# data_proV2_0_-_A.net
KiCad netlist of a schematic drawn in EAGLE
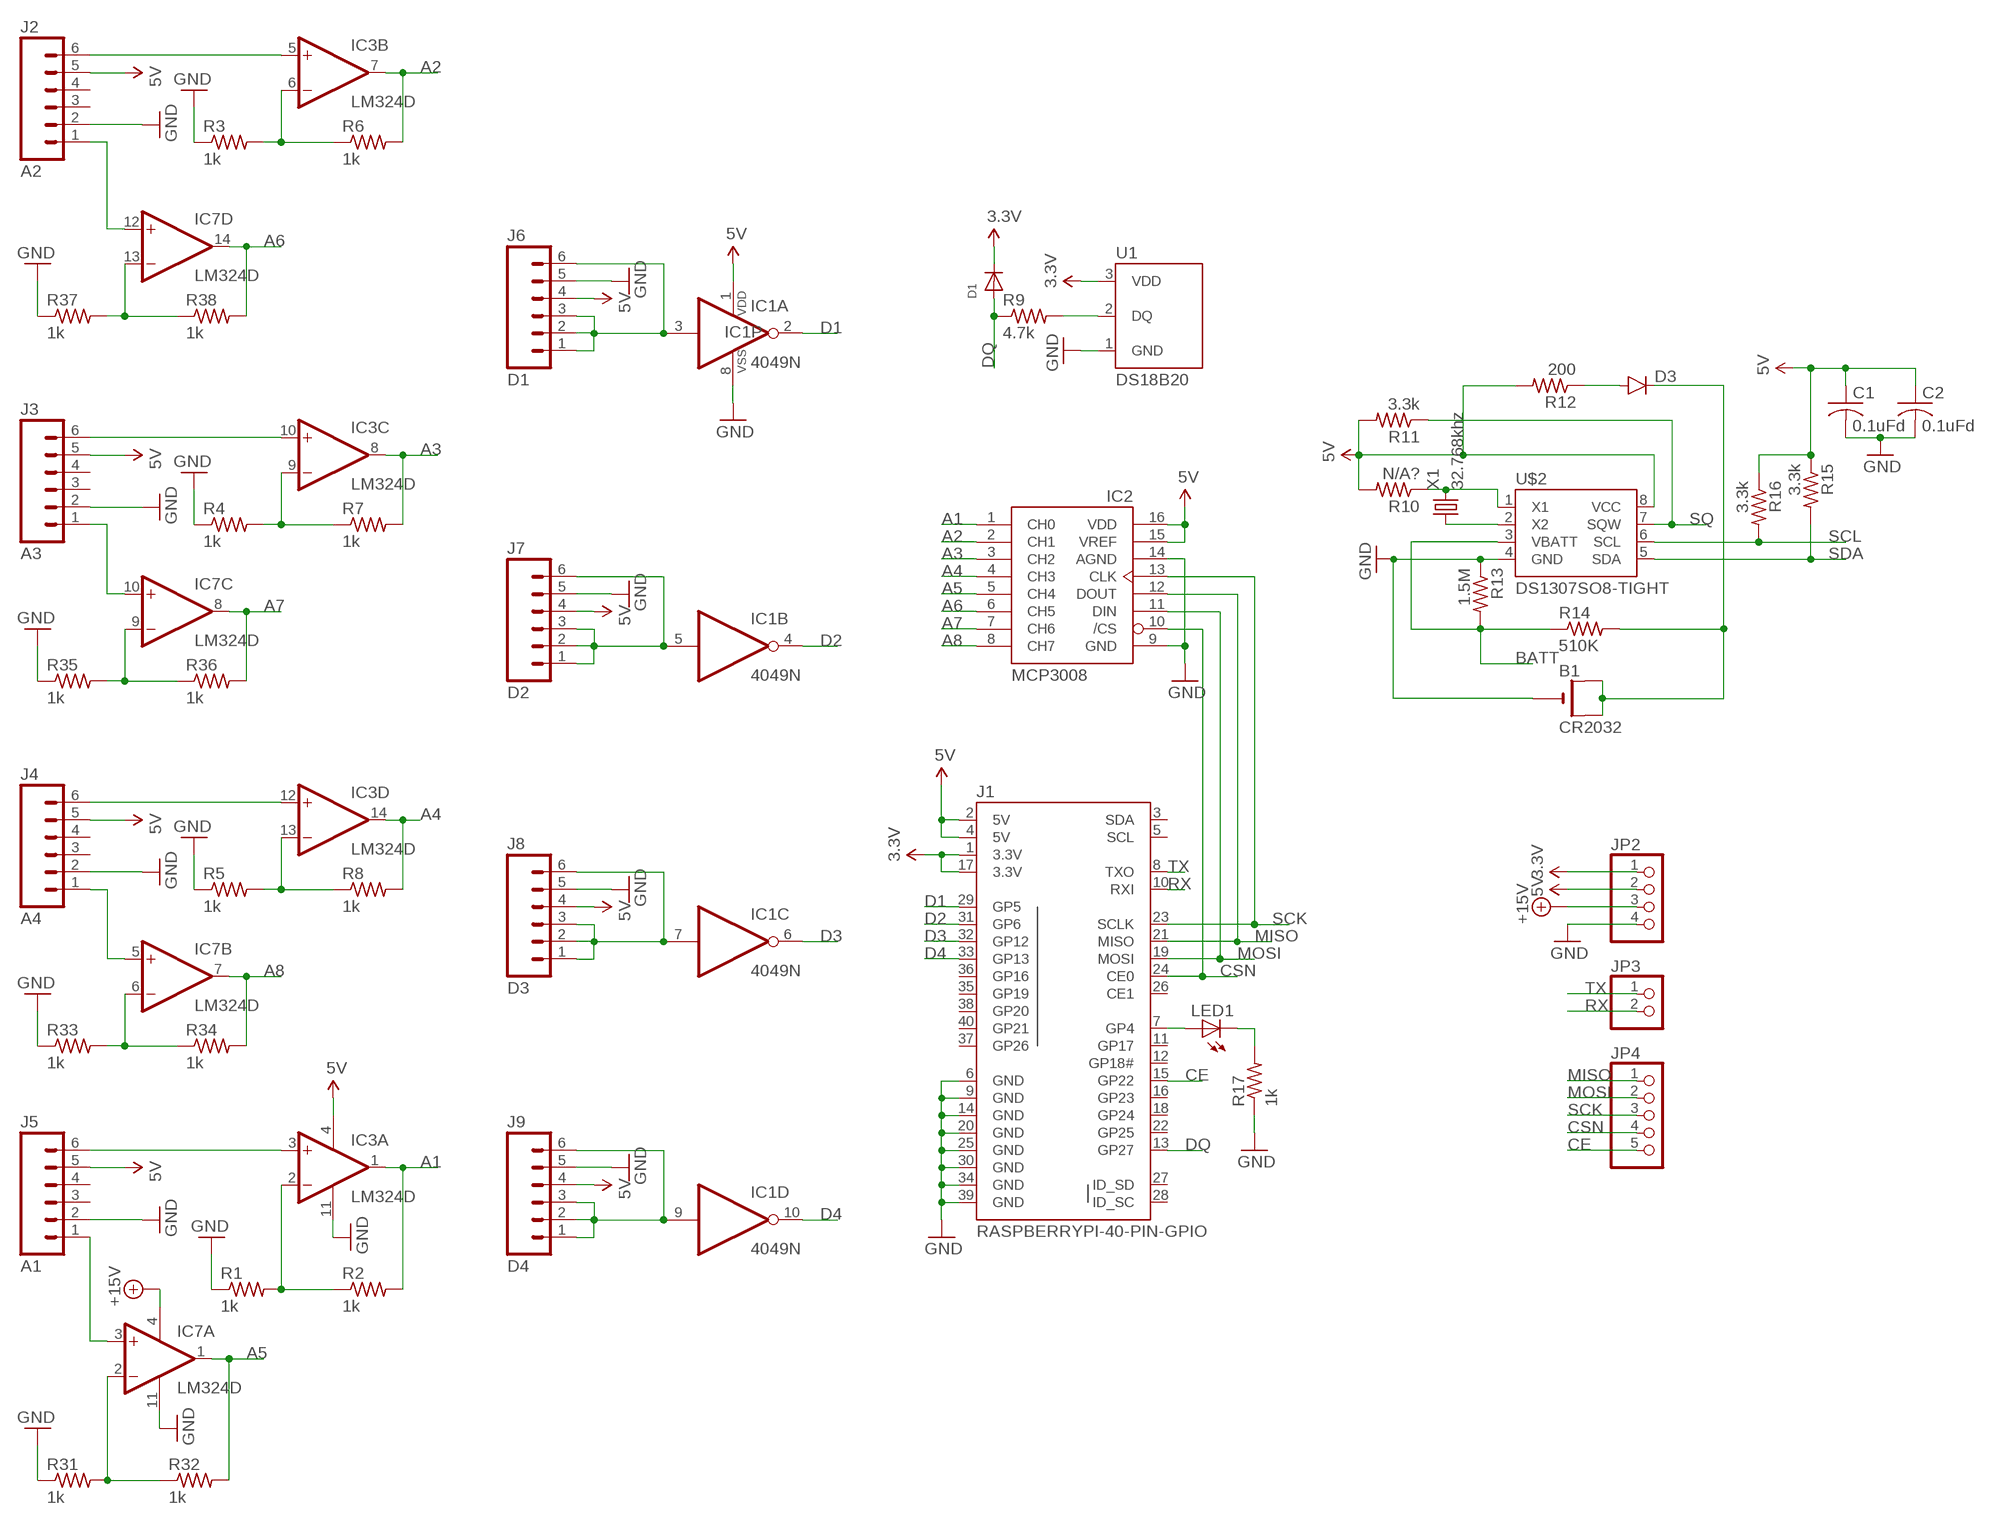
[diagram p0: schematic, sheet 1]

(export (version "E")
  (design (tool "Eeschema 10.0.6"))
  (components
    (comp (ref "B1")
      (value "CR2032")
      (footprint "eagle-import:CR2032-SMD")
      (libsource (lib "eagle-import") (part "CR2032SMT"))
    )
    (comp (ref "C1")
      (value "0.1uFd")
      (footprint "eagle-import:C0805")
      (libsource (lib "eagle-import") (part "C-USC0805"))
    )
    (comp (ref "C2")
      (value "0.1uFd")
      (footprint "eagle-import:C0805")
      (libsource (lib "eagle-import") (part "C-USC0805"))
    )
    (comp (ref "D1")
      (value "DIODESOD-323F")
      (footprint "eagle-import:SOD-323F")
      (libsource (lib "eagle-import") (part "DIODESOD-323F"))
    )
    (comp (ref "D3")
      (value "DIODESMB")
      (footprint "eagle-import:SMB-DIODE")
      (libsource (lib "eagle-import") (part "DIODESMB"))
    )
    (comp (ref "IC1")
      (value "4049N")
      (footprint "eagle-import:DIL16")
      (libsource (lib "eagle-import") (part "4049N"))
    )
    (comp (ref "IC2")
      (value "MCP3008")
      (footprint "eagle-import:DIL16")
      (libsource (lib "eagle-import") (part "MCP3008"))
    )
    (comp (ref "IC3")
      (value "LM324D")
      (footprint "eagle-import:SO14")
      (libsource (lib "eagle-import") (part "LM324D"))
    )
    (comp (ref "IC7")
      (value "LM324D")
      (footprint "eagle-import:SO14")
      (libsource (lib "eagle-import") (part "LM324D"))
    )
    (comp (ref "J1")
      (value "RASPBERRYPI-40-PIN-GPIO")
      (footprint "eagle-import:2X20-SHROUDED")
      (libsource (lib "eagle-import") (part "RASPBERRYPI-40-PIN-GPIO"))
    )
    (comp (ref "J2")
      (value "A2")
      (footprint "eagle-import:BTA")
      (libsource (lib "eagle-import") (part "M06VERNIER-ANALOG"))
    )
    (comp (ref "J3")
      (value "A3")
      (footprint "eagle-import:BTA")
      (libsource (lib "eagle-import") (part "M06VERNIER-ANALOG"))
    )
    (comp (ref "J4")
      (value "A4")
      (footprint "eagle-import:BTA")
      (libsource (lib "eagle-import") (part "M06VERNIER-ANALOG"))
    )
    (comp (ref "J5")
      (value "A1")
      (footprint "eagle-import:BTA")
      (libsource (lib "eagle-import") (part "M06VERNIER-ANALOG"))
    )
    (comp (ref "J6")
      (value "D1")
      (footprint "eagle-import:BTD")
      (libsource (lib "eagle-import") (part "M06VERNIER-DIGITAL"))
    )
    (comp (ref "J7")
      (value "D2")
      (footprint "eagle-import:BTD")
      (libsource (lib "eagle-import") (part "M06VERNIER-DIGITAL"))
    )
    (comp (ref "J8")
      (value "D3")
      (footprint "eagle-import:BTD")
      (libsource (lib "eagle-import") (part "M06VERNIER-DIGITAL"))
    )
    (comp (ref "J9")
      (value "D4")
      (footprint "eagle-import:BTD")
      (libsource (lib "eagle-import") (part "M06VERNIER-DIGITAL"))
    )
    (comp (ref "JP2")
      (value "PINHD-1X4")
      (footprint "eagle-import:1X04")
      (libsource (lib "eagle-import") (part "PINHD-1X4"))
    )
    (comp (ref "JP3")
      (value "PINHD-1X2")
      (footprint "eagle-import:1X02")
      (libsource (lib "eagle-import") (part "PINHD-1X2"))
    )
    (comp (ref "JP4")
      (value "PINHD-1X5")
      (footprint "eagle-import:1X05")
      (libsource (lib "eagle-import") (part "PINHD-1X5"))
    )
    (comp (ref "LED1")
      (value "LEDCHIP-LED0805")
      (footprint "eagle-import:CHIP-LED0805")
      (libsource (lib "eagle-import") (part "LEDCHIP-LED0805"))
    )
    (comp (ref "R1")
      (value "1k")
      (footprint "eagle-import:R0805")
      (libsource (lib "eagle-import") (part "resistor_R-US_R0805"))
    )
    (comp (ref "R2")
      (value "1k")
      (footprint "eagle-import:R0805")
      (libsource (lib "eagle-import") (part "resistor_R-US_R0805"))
    )
    (comp (ref "R3")
      (value "1k")
      (footprint "eagle-import:R0805")
      (libsource (lib "eagle-import") (part "resistor_R-US_R0805"))
    )
    (comp (ref "R4")
      (value "1k")
      (footprint "eagle-import:R0805")
      (libsource (lib "eagle-import") (part "resistor_R-US_R0805"))
    )
    (comp (ref "R5")
      (value "1k")
      (footprint "eagle-import:R0805")
      (libsource (lib "eagle-import") (part "resistor_R-US_R0805"))
    )
    (comp (ref "R6")
      (value "1k")
      (footprint "eagle-import:R0805")
      (libsource (lib "eagle-import") (part "resistor_R-US_R0805"))
    )
    (comp (ref "R7")
      (value "1k")
      (footprint "eagle-import:R0805")
      (libsource (lib "eagle-import") (part "resistor_R-US_R0805"))
    )
    (comp (ref "R8")
      (value "1k")
      (footprint "eagle-import:R0805")
      (libsource (lib "eagle-import") (part "resistor_R-US_R0805"))
    )
    (comp (ref "R9")
      (value "4.7k")
      (footprint "eagle-import:R0805")
      (libsource (lib "eagle-import") (part "resistor_R-US_R0805"))
    )
    (comp (ref "R10")
      (value "N/A?")
      (footprint "eagle-import:R0805")
      (libsource (lib "eagle-import") (part "R-US_R0805"))
    )
    (comp (ref "R11")
      (value "3.3k")
      (footprint "eagle-import:R0805")
      (libsource (lib "eagle-import") (part "R-US_R0805"))
    )
    (comp (ref "R12")
      (value "200")
      (footprint "eagle-import:R0805")
      (libsource (lib "eagle-import") (part "R-US_R0805"))
    )
    (comp (ref "R13")
      (value "1.5M")
      (footprint "eagle-import:R0805")
      (libsource (lib "eagle-import") (part "R-US_R0805"))
    )
    (comp (ref "R14")
      (value "510K")
      (footprint "eagle-import:R0805")
      (libsource (lib "eagle-import") (part "R-US_R0805"))
    )
    (comp (ref "R15")
      (value "3.3k")
      (footprint "eagle-import:R0805")
      (libsource (lib "eagle-import") (part "R-US_R0805"))
    )
    (comp (ref "R16")
      (value "3.3k")
      (footprint "eagle-import:R0805")
      (libsource (lib "eagle-import") (part "R-US_R0805"))
    )
    (comp (ref "R17")
      (value "1k")
      (footprint "eagle-import:R0805")
      (libsource (lib "eagle-import") (part "R-US_R0805"))
    )
    (comp (ref "R31")
      (value "1k")
      (footprint "eagle-import:R0805")
      (libsource (lib "eagle-import") (part "resistor_R-US_R0805"))
    )
    (comp (ref "R32")
      (value "1k")
      (footprint "eagle-import:R0805")
      (libsource (lib "eagle-import") (part "resistor_R-US_R0805"))
    )
    (comp (ref "R33")
      (value "1k")
      (footprint "eagle-import:R0805")
      (libsource (lib "eagle-import") (part "resistor_R-US_R0805"))
    )
    (comp (ref "R34")
      (value "1k")
      (footprint "eagle-import:R0805")
      (libsource (lib "eagle-import") (part "resistor_R-US_R0805"))
    )
    (comp (ref "R35")
      (value "1k")
      (footprint "eagle-import:R0805")
      (libsource (lib "eagle-import") (part "resistor_R-US_R0805"))
    )
    (comp (ref "R36")
      (value "1k")
      (footprint "eagle-import:R0805")
      (libsource (lib "eagle-import") (part "resistor_R-US_R0805"))
    )
    (comp (ref "R37")
      (value "1k")
      (footprint "eagle-import:R0805")
      (libsource (lib "eagle-import") (part "resistor_R-US_R0805"))
    )
    (comp (ref "R38")
      (value "1k")
      (footprint "eagle-import:R0805")
      (libsource (lib "eagle-import") (part "resistor_R-US_R0805"))
    )
    (comp (ref "U$2")
      (value "DS1307SO8-TIGHT")
      (footprint "eagle-import:SO08-TIGHT")
      (libsource (lib "eagle-import") (part "DS1307SO8-TIGHT"))
    )
    (comp (ref "U1")
      (value "DS18B20")
      (footprint "eagle-import:TO-92-AMMO")
      (libsource (lib "eagle-import") (part "DS18B20"))
    )
    (comp (ref "X1")
      (value "32.768khz")
      (footprint "eagle-import:TC38H")
      (libsource (lib "eagle-import") (part "CRYSTALTC38H"))
    )
  )
  (nets
    (net (code "1") (name "+15V") (class "Default")
      (node (ref "IC7") (pin "4") (pinfunction "V+_4") (pintype "power_in"))
      (node (ref "JP2") (pin "3") (pinfunction "3_3") (pintype "passive"))
    )
    (net (code "2") (name "/A1") (class "Default")
      (node (ref "IC2") (pin "1") (pinfunction "CH0_1") (pintype "input"))
      (node (ref "IC3") (pin "1") (pinfunction "OUT_1") (pintype "output"))
      (node (ref "R2") (pin "2") (pinfunction "2_2") (pintype "passive"))
    )
    (net (code "3") (name "/A2") (class "Default")
      (node (ref "IC2") (pin "2") (pinfunction "CH1_2") (pintype "input"))
      (node (ref "IC3") (pin "7") (pinfunction "OUT_7") (pintype "output"))
      (node (ref "R6") (pin "2") (pinfunction "2_2") (pintype "passive"))
    )
    (net (code "4") (name "/A3") (class "Default")
      (node (ref "IC2") (pin "3") (pinfunction "CH2_3") (pintype "input"))
      (node (ref "IC3") (pin "8") (pinfunction "OUT_8") (pintype "output"))
      (node (ref "R7") (pin "2") (pinfunction "2_2") (pintype "passive"))
    )
    (net (code "5") (name "/A4") (class "Default")
      (node (ref "IC2") (pin "4") (pinfunction "CH3_4") (pintype "input"))
      (node (ref "IC3") (pin "14") (pinfunction "OUT_14") (pintype "output"))
      (node (ref "R8") (pin "2") (pinfunction "2_2") (pintype "passive"))
    )
    (net (code "6") (name "/A5") (class "Default")
      (node (ref "IC2") (pin "5") (pinfunction "CH4_5") (pintype "input"))
      (node (ref "IC7") (pin "1") (pinfunction "OUT_1") (pintype "output"))
      (node (ref "R32") (pin "2") (pinfunction "2_2") (pintype "passive"))
    )
    (net (code "7") (name "/A6") (class "Default")
      (node (ref "IC2") (pin "6") (pinfunction "CH5_6") (pintype "input"))
      (node (ref "IC7") (pin "14") (pinfunction "OUT_14") (pintype "output"))
      (node (ref "R38") (pin "2") (pinfunction "2_2") (pintype "passive"))
    )
    (net (code "8") (name "/A7") (class "Default")
      (node (ref "IC2") (pin "7") (pinfunction "CH6_7") (pintype "input"))
      (node (ref "IC7") (pin "8") (pinfunction "OUT_8") (pintype "output"))
      (node (ref "R36") (pin "2") (pinfunction "2_2") (pintype "passive"))
    )
    (net (code "9") (name "/A8") (class "Default")
      (node (ref "IC2") (pin "8") (pinfunction "CH7_8") (pintype "input"))
      (node (ref "IC7") (pin "7") (pinfunction "OUT_7") (pintype "output"))
      (node (ref "R34") (pin "2") (pinfunction "2_2") (pintype "passive"))
    )
    (net (code "10") (name "/BATT") (class "Default")
      (node (ref "R13") (pin "2") (pinfunction "2_2") (pintype "passive"))
      (node (ref "R14") (pin "1") (pinfunction "1_1") (pintype "passive"))
      (node (ref "U$2") (pin "3") (pinfunction "VBATT_3") (pintype "bidirectional"))
    )
    (net (code "11") (name "/CE") (class "Default")
      (node (ref "J1") (pin "15") (pinfunction "GP22_15") (pintype "bidirectional"))
      (node (ref "JP4") (pin "5") (pinfunction "5_5") (pintype "passive"))
    )
    (net (code "12") (name "/CSN") (class "Default")
      (node (ref "IC2") (pin "10") (pinfunction "/CS_10") (pintype "input"))
      (node (ref "J1") (pin "24") (pinfunction "CE0_24") (pintype "output"))
      (node (ref "JP4") (pin "4") (pinfunction "4_4") (pintype "passive"))
    )
    (net (code "13") (name "/D1") (class "Default")
      (node (ref "IC1") (pin "2") (pinfunction "O_2") (pintype "output"))
      (node (ref "J1") (pin "29") (pinfunction "GP5_29") (pintype "bidirectional"))
    )
    (net (code "14") (name "/D2") (class "Default")
      (node (ref "IC1") (pin "4") (pinfunction "O_4") (pintype "output"))
      (node (ref "J1") (pin "31") (pinfunction "GP6_31") (pintype "bidirectional"))
    )
    (net (code "15") (name "/D3") (class "Default")
      (node (ref "IC1") (pin "6") (pinfunction "O_6") (pintype "output"))
      (node (ref "J1") (pin "32") (pinfunction "GP12_32") (pintype "bidirectional"))
    )
    (net (code "16") (name "/D4") (class "Default")
      (node (ref "IC1") (pin "10") (pinfunction "O_10") (pintype "output"))
      (node (ref "J1") (pin "33") (pinfunction "GP13_33") (pintype "bidirectional"))
    )
    (net (code "17") (name "/DQ") (class "Default")
      (node (ref "D1") (pin "A") (pinfunction "A_A") (pintype "passive"))
      (node (ref "J1") (pin "13") (pinfunction "GP27_13") (pintype "bidirectional"))
      (node (ref "R9") (pin "1") (pinfunction "1_1") (pintype "passive"))
    )
    (net (code "18") (name "/MISO") (class "Default")
      (node (ref "IC2") (pin "12") (pinfunction "DOUT_12") (pintype "output"))
      (node (ref "J1") (pin "21") (pinfunction "MISO_21") (pintype "input"))
      (node (ref "JP4") (pin "1") (pinfunction "1_1") (pintype "passive"))
    )
    (net (code "19") (name "/MOSI") (class "Default")
      (node (ref "IC2") (pin "11") (pinfunction "DIN_11") (pintype "input"))
      (node (ref "J1") (pin "19") (pinfunction "MOSI_19") (pintype "output"))
      (node (ref "JP4") (pin "2") (pinfunction "2_2") (pintype "passive"))
    )
    (net (code "20") (name "/RX") (class "Default")
      (node (ref "J1") (pin "10") (pinfunction "RXI_10") (pintype "input"))
      (node (ref "JP3") (pin "2") (pinfunction "2_2") (pintype "passive"))
    )
    (net (code "21") (name "/SCK") (class "Default")
      (node (ref "IC2") (pin "13") (pinfunction "CLK_13") (pintype "input"))
      (node (ref "J1") (pin "23") (pinfunction "SCLK_23") (pintype "output"))
      (node (ref "JP4") (pin "3") (pinfunction "3_3") (pintype "passive"))
    )
    (net (code "22") (name "/SCL") (class "Default")
      (node (ref "R16") (pin "2") (pinfunction "2_2") (pintype "passive"))
      (node (ref "U$2") (pin "6") (pinfunction "SCL_6") (pintype "bidirectional"))
    )
    (net (code "23") (name "/SDA") (class "Default")
      (node (ref "R15") (pin "2") (pinfunction "2_2") (pintype "passive"))
      (node (ref "U$2") (pin "5") (pinfunction "SDA_5") (pintype "bidirectional"))
    )
    (net (code "24") (name "/SQ") (class "Default")
      (node (ref "R11") (pin "1") (pinfunction "1_1") (pintype "passive"))
      (node (ref "U$2") (pin "7") (pinfunction "SQW_7") (pintype "bidirectional"))
    )
    (net (code "25") (name "/TX") (class "Default")
      (node (ref "J1") (pin "8") (pinfunction "TXO_8") (pintype "output"))
      (node (ref "JP3") (pin "1") (pinfunction "1_1") (pintype "passive"))
    )
    (net (code "26") (name "3.3V") (class "Default")
      (node (ref "D1") (pin "C") (pinfunction "C_C") (pintype "passive"))
      (node (ref "J1") (pin "1") (pinfunction "3.3V_1") (pintype "power_in"))
      (node (ref "J1") (pin "17") (pinfunction "3.3V_17") (pintype "power_in"))
      (node (ref "JP2") (pin "1") (pinfunction "1_1") (pintype "passive"))
      (node (ref "U1") (pin "3") (pinfunction "VDD_3") (pintype "power_in"))
    )
    (net (code "27") (name "5V") (class "Default")
      (node (ref "C1") (pin "1") (pinfunction "1_1") (pintype "passive"))
      (node (ref "C2") (pin "1") (pinfunction "1_1") (pintype "passive"))
      (node (ref "IC1") (pin "1") (pinfunction "VDD_1") (pintype "power_in"))
      (node (ref "IC2") (pin "15") (pinfunction "VREF_15") (pintype "input"))
      (node (ref "IC2") (pin "16") (pinfunction "VDD_16") (pintype "power_in"))
      (node (ref "IC3") (pin "4") (pinfunction "V+_4") (pintype "power_in"))
      (node (ref "J1") (pin "2") (pinfunction "5V_2") (pintype "power_in"))
      (node (ref "J1") (pin "4") (pinfunction "5V_4") (pintype "power_in"))
      (node (ref "J2") (pin "5") (pinfunction "5_5") (pintype "passive"))
      (node (ref "J3") (pin "5") (pinfunction "5_5") (pintype "passive"))
      (node (ref "J4") (pin "5") (pinfunction "5_5") (pintype "passive"))
      (node (ref "J5") (pin "5") (pinfunction "5_5") (pintype "passive"))
      (node (ref "J6") (pin "4") (pinfunction "4_4") (pintype "passive"))
      (node (ref "J7") (pin "4") (pinfunction "4_4") (pintype "passive"))
      (node (ref "J8") (pin "4") (pinfunction "4_4") (pintype "passive"))
      (node (ref "J9") (pin "4") (pinfunction "4_4") (pintype "passive"))
      (node (ref "JP2") (pin "2") (pinfunction "2_2") (pintype "passive"))
      (node (ref "R10") (pin "2") (pinfunction "2_2") (pintype "passive"))
      (node (ref "R11") (pin "2") (pinfunction "2_2") (pintype "passive"))
      (node (ref "R12") (pin "2") (pinfunction "2_2") (pintype "passive"))
      (node (ref "R15") (pin "1") (pinfunction "1_1") (pintype "passive"))
      (node (ref "R16") (pin "1") (pinfunction "1_1") (pintype "passive"))
      (node (ref "U$2") (pin "8") (pinfunction "VCC_8") (pintype "bidirectional"))
    )
    (net (code "28") (name "GND") (class "Default")
      (node (ref "B1") (pin "-") (pinfunction "-_-") (pintype "passive"))
      (node (ref "C1") (pin "2") (pinfunction "2_2") (pintype "passive"))
      (node (ref "C2") (pin "2") (pinfunction "2_2") (pintype "passive"))
      (node (ref "IC1") (pin "8") (pinfunction "VSS_8") (pintype "power_in"))
      (node (ref "IC2") (pin "14") (pinfunction "AGND_14") (pintype "power_in"))
      (node (ref "IC2") (pin "9") (pinfunction "GND_9") (pintype "power_in"))
      (node (ref "IC3") (pin "11") (pinfunction "V-_11") (pintype "power_in"))
      (node (ref "IC7") (pin "11") (pinfunction "V-_11") (pintype "power_in"))
      (node (ref "J1") (pin "14") (pinfunction "GND_14") (pintype "power_in"))
      (node (ref "J1") (pin "20") (pinfunction "GND_20") (pintype "power_in"))
      (node (ref "J1") (pin "25") (pinfunction "GND_25") (pintype "power_in"))
      (node (ref "J1") (pin "30") (pinfunction "GND_30") (pintype "power_in"))
      (node (ref "J1") (pin "34") (pinfunction "GND_34") (pintype "power_in"))
      (node (ref "J1") (pin "39") (pinfunction "GND_39") (pintype "power_in"))
      (node (ref "J1") (pin "6") (pinfunction "GND_6") (pintype "power_in"))
      (node (ref "J1") (pin "9") (pinfunction "GND_9") (pintype "power_in"))
      (node (ref "J2") (pin "2") (pinfunction "2_2") (pintype "passive"))
      (node (ref "J3") (pin "2") (pinfunction "2_2") (pintype "passive"))
      (node (ref "J4") (pin "2") (pinfunction "2_2") (pintype "passive"))
      (node (ref "J5") (pin "2") (pinfunction "2_2") (pintype "passive"))
      (node (ref "J6") (pin "5") (pinfunction "5_5") (pintype "passive"))
      (node (ref "J7") (pin "5") (pinfunction "5_5") (pintype "passive"))
      (node (ref "J8") (pin "5") (pinfunction "5_5") (pintype "passive"))
      (node (ref "J9") (pin "5") (pinfunction "5_5") (pintype "passive"))
      (node (ref "JP2") (pin "4") (pinfunction "4_4") (pintype "passive"))
      (node (ref "R1") (pin "1") (pinfunction "1_1") (pintype "passive"))
      (node (ref "R13") (pin "1") (pinfunction "1_1") (pintype "passive"))
      (node (ref "R17") (pin "1") (pinfunction "1_1") (pintype "passive"))
      (node (ref "R3") (pin "1") (pinfunction "1_1") (pintype "passive"))
      (node (ref "R31") (pin "1") (pinfunction "1_1") (pintype "passive"))
      (node (ref "R33") (pin "1") (pinfunction "1_1") (pintype "passive"))
      (node (ref "R35") (pin "1") (pinfunction "1_1") (pintype "passive"))
      (node (ref "R37") (pin "1") (pinfunction "1_1") (pintype "passive"))
      (node (ref "R4") (pin "1") (pinfunction "1_1") (pintype "passive"))
      (node (ref "R5") (pin "1") (pinfunction "1_1") (pintype "passive"))
      (node (ref "U$2") (pin "4") (pinfunction "GND_4") (pintype "bidirectional"))
      (node (ref "U1") (pin "1") (pinfunction "GND_1") (pintype "power_in"))
    )
    (net (code "29") (name "Net-(B1-+)") (class "Default")
      (node (ref "B1") (pin "+$1") (pinfunction "+_+$1") (pintype "passive"))
      (node (ref "B1") (pin "+$2") (pinfunction "+1_+$2") (pintype "passive"))
      (node (ref "D3") (pin "C") (pinfunction "C_C") (pintype "passive"))
      (node (ref "R14") (pin "2") (pinfunction "2_2") (pintype "passive"))
    )
    (net (code "30") (name "Net-(D3-PadA)") (class "Default")
      (node (ref "D3") (pin "A") (pinfunction "A_A") (pintype "passive"))
      (node (ref "R12") (pin "1") (pinfunction "1_1") (pintype "passive"))
    )
    (net (code "31") (name "Net-(IC1A-I)") (class "Default")
      (node (ref "IC1") (pin "3") (pinfunction "I_3") (pintype "input"))
      (node (ref "J6") (pin "1") (pinfunction "1_1") (pintype "passive"))
      (node (ref "J6") (pin "2") (pinfunction "2_2") (pintype "passive"))
      (node (ref "J6") (pin "3") (pinfunction "3_3") (pintype "passive"))
      (node (ref "J6") (pin "6") (pinfunction "6_6") (pintype "passive"))
    )
    (net (code "32") (name "Net-(IC1B-I)") (class "Default")
      (node (ref "IC1") (pin "5") (pinfunction "I_5") (pintype "input"))
      (node (ref "J7") (pin "1") (pinfunction "1_1") (pintype "passive"))
      (node (ref "J7") (pin "2") (pinfunction "2_2") (pintype "passive"))
      (node (ref "J7") (pin "3") (pinfunction "3_3") (pintype "passive"))
      (node (ref "J7") (pin "6") (pinfunction "6_6") (pintype "passive"))
    )
    (net (code "33") (name "Net-(IC1C-I)") (class "Default")
      (node (ref "IC1") (pin "7") (pinfunction "I_7") (pintype "input"))
      (node (ref "J8") (pin "1") (pinfunction "1_1") (pintype "passive"))
      (node (ref "J8") (pin "2") (pinfunction "2_2") (pintype "passive"))
      (node (ref "J8") (pin "3") (pinfunction "3_3") (pintype "passive"))
      (node (ref "J8") (pin "6") (pinfunction "6_6") (pintype "passive"))
    )
    (net (code "34") (name "Net-(IC1D-I)") (class "Default")
      (node (ref "IC1") (pin "9") (pinfunction "I_9") (pintype "input"))
      (node (ref "J9") (pin "1") (pinfunction "1_1") (pintype "passive"))
      (node (ref "J9") (pin "2") (pinfunction "2_2") (pintype "passive"))
      (node (ref "J9") (pin "3") (pinfunction "3_3") (pintype "passive"))
      (node (ref "J9") (pin "6") (pinfunction "6_6") (pintype "passive"))
    )
    (net (code "35") (name "Net-(IC3A-+IN)") (class "Default")
      (node (ref "IC3") (pin "3") (pinfunction "+IN_3") (pintype "input"))
      (node (ref "J5") (pin "6") (pinfunction "6_6") (pintype "passive"))
    )
    (net (code "36") (name "Net-(IC3A--IN)") (class "Default")
      (node (ref "IC3") (pin "2") (pinfunction "-IN_2") (pintype "input"))
      (node (ref "R1") (pin "2") (pinfunction "2_2") (pintype "passive"))
      (node (ref "R2") (pin "1") (pinfunction "1_1") (pintype "passive"))
    )
    (net (code "37") (name "Net-(IC3B-+IN)") (class "Default")
      (node (ref "IC3") (pin "5") (pinfunction "+IN_5") (pintype "input"))
      (node (ref "J2") (pin "6") (pinfunction "6_6") (pintype "passive"))
    )
    (net (code "38") (name "Net-(IC3B--IN)") (class "Default")
      (node (ref "IC3") (pin "6") (pinfunction "-IN_6") (pintype "input"))
      (node (ref "R3") (pin "2") (pinfunction "2_2") (pintype "passive"))
      (node (ref "R6") (pin "1") (pinfunction "1_1") (pintype "passive"))
    )
    (net (code "39") (name "Net-(IC3C-+IN)") (class "Default")
      (node (ref "IC3") (pin "10") (pinfunction "+IN_10") (pintype "input"))
      (node (ref "J3") (pin "6") (pinfunction "6_6") (pintype "passive"))
    )
    (net (code "40") (name "Net-(IC3C--IN)") (class "Default")
      (node (ref "IC3") (pin "9") (pinfunction "-IN_9") (pintype "input"))
      (node (ref "R4") (pin "2") (pinfunction "2_2") (pintype "passive"))
      (node (ref "R7") (pin "1") (pinfunction "1_1") (pintype "passive"))
    )
    (net (code "41") (name "Net-(IC3D-+IN)") (class "Default")
      (node (ref "IC3") (pin "12") (pinfunction "+IN_12") (pintype "input"))
      (node (ref "J4") (pin "6") (pinfunction "6_6") (pintype "passive"))
    )
    (net (code "42") (name "Net-(IC3D--IN)") (class "Default")
      (node (ref "IC3") (pin "13") (pinfunction "-IN_13") (pintype "input"))
      (node (ref "R5") (pin "2") (pinfunction "2_2") (pintype "passive"))
      (node (ref "R8") (pin "1") (pinfunction "1_1") (pintype "passive"))
    )
    (net (code "43") (name "Net-(IC7A-+IN)") (class "Default")
      (node (ref "IC7") (pin "3") (pinfunction "+IN_3") (pintype "input"))
      (node (ref "J5") (pin "1") (pinfunction "1_1") (pintype "passive"))
    )
    (net (code "44") (name "Net-(IC7A--IN)") (class "Default")
      (node (ref "IC7") (pin "2") (pinfunction "-IN_2") (pintype "input"))
      (node (ref "R31") (pin "2") (pinfunction "2_2") (pintype "passive"))
      (node (ref "R32") (pin "1") (pinfunction "1_1") (pintype "passive"))
    )
    (net (code "45") (name "Net-(IC7B-+IN)") (class "Default")
      (node (ref "IC7") (pin "5") (pinfunction "+IN_5") (pintype "input"))
      (node (ref "J4") (pin "1") (pinfunction "1_1") (pintype "passive"))
    )
    (net (code "46") (name "Net-(IC7B--IN)") (class "Default")
      (node (ref "IC7") (pin "6") (pinfunction "-IN_6") (pintype "input"))
      (node (ref "R33") (pin "2") (pinfunction "2_2") (pintype "passive"))
      (node (ref "R34") (pin "1") (pinfunction "1_1") (pintype "passive"))
    )
    (net (code "47") (name "Net-(IC7C-+IN)") (class "Default")
      (node (ref "IC7") (pin "10") (pinfunction "+IN_10") (pintype "input"))
      (node (ref "J3") (pin "1") (pinfunction "1_1") (pintype "passive"))
    )
    (net (code "48") (name "Net-(IC7C--IN)") (class "Default")
      (node (ref "IC7") (pin "9") (pinfunction "-IN_9") (pintype "input"))
      (node (ref "R35") (pin "2") (pinfunction "2_2") (pintype "passive"))
      (node (ref "R36") (pin "1") (pinfunction "1_1") (pintype "passive"))
    )
    (net (code "49") (name "Net-(IC7D-+IN)") (class "Default")
      (node (ref "IC7") (pin "12") (pinfunction "+IN_12") (pintype "input"))
      (node (ref "J2") (pin "1") (pinfunction "1_1") (pintype "passive"))
    )
    (net (code "50") (name "Net-(IC7D--IN)") (class "Default")
      (node (ref "IC7") (pin "13") (pinfunction "-IN_13") (pintype "input"))
      (node (ref "R37") (pin "2") (pinfunction "2_2") (pintype "passive"))
      (node (ref "R38") (pin "1") (pinfunction "1_1") (pintype "passive"))
    )
    (net (code "51") (name "Net-(J1-GP4)") (class "Default")
      (node (ref "J1") (pin "7") (pinfunction "GP4_7") (pintype "bidirectional"))
      (node (ref "LED1") (pin "A") (pinfunction "A_A") (pintype "passive"))
    )
    (net (code "52") (name "Net-(LED1-PadC)") (class "Default")
      (node (ref "LED1") (pin "C") (pinfunction "C_C") (pintype "passive"))
      (node (ref "R17") (pin "2") (pinfunction "2_2") (pintype "passive"))
    )
    (net (code "53") (name "Net-(U$2-X1)") (class "Default")
      (node (ref "R10") (pin "1") (pinfunction "1_1") (pintype "passive"))
      (node (ref "U$2") (pin "1") (pinfunction "X1_1") (pintype "bidirectional"))
      (node (ref "X1") (pin "2") (pinfunction "2_2") (pintype "passive"))
    )
    (net (code "54") (name "Net-(U$2-X2)") (class "Default")
      (node (ref "U$2") (pin "2") (pinfunction "X2_2") (pintype "bidirectional"))
      (node (ref "X1") (pin "1") (pinfunction "1_1") (pintype "passive"))
    )
    (net (code "55") (name "Net-(U1-DQ)") (class "Default")
      (node (ref "R9") (pin "2") (pinfunction "2_2") (pintype "passive"))
      (node (ref "U1") (pin "2") (pinfunction "DQ_2") (pintype "bidirectional"))
    )
    (net (code "56") (name "unconnected-(J1-CE1-Pad26)") (class "Default")
      (node (ref "J1") (pin "26") (pinfunction "CE1_26") (pintype "output"))
    )
    (net (code "57") (name "unconnected-(J1-GP16-Pad36)") (class "Default")
      (node (ref "J1") (pin "36") (pinfunction "GP16_36") (pintype "bidirectional"))
    )
    (net (code "58") (name "unconnected-(J1-GP17-Pad11)") (class "Default")
      (node (ref "J1") (pin "11") (pinfunction "GP17_11") (pintype "bidirectional"))
    )
    (net (code "59") (name "unconnected-(J1-GP18#-Pad12)") (class "Default")
      (node (ref "J1") (pin "12") (pinfunction "GP18#_12") (pintype "bidirectional"))
    )
    (net (code "60") (name "unconnected-(J1-GP19-Pad35)") (class "Default")
      (node (ref "J1") (pin "35") (pinfunction "GP19_35") (pintype "bidirectional"))
    )
    (net (code "61") (name "unconnected-(J1-GP20-Pad38)") (class "Default")
      (node (ref "J1") (pin "38") (pinfunction "GP20_38") (pintype "bidirectional"))
    )
    (net (code "62") (name "unconnected-(J1-GP21-Pad40)") (class "Default")
      (node (ref "J1") (pin "40") (pinfunction "GP21_40") (pintype "bidirectional"))
    )
    (net (code "63") (name "unconnected-(J1-GP23-Pad16)") (class "Default")
      (node (ref "J1") (pin "16") (pinfunction "GP23_16") (pintype "bidirectional"))
    )
    (net (code "64") (name "unconnected-(J1-GP24-Pad18)") (class "Default")
      (node (ref "J1") (pin "18") (pinfunction "GP24_18") (pintype "bidirectional"))
    )
    (net (code "65") (name "unconnected-(J1-GP25-Pad22)") (class "Default")
      (node (ref "J1") (pin "22") (pinfunction "GP25_22") (pintype "bidirectional"))
    )
    (net (code "66") (name "unconnected-(J1-GP26-Pad37)") (class "Default")
      (node (ref "J1") (pin "37") (pinfunction "GP26_37") (pintype "bidirectional"))
    )
    (net (code "67") (name "unconnected-(J1-ID_SC-Pad28)") (class "Default")
      (node (ref "J1") (pin "28") (pinfunction "ID_SC_28") (pintype "bidirectional"))
    )
    (net (code "68") (name "unconnected-(J1-ID_SD-Pad27)") (class "Default")
      (node (ref "J1") (pin "27") (pinfunction "ID_SD_27") (pintype "bidirectional"))
    )
    (net (code "69") (name "unconnected-(J1-SCL-Pad5)") (class "Default")
      (node (ref "J1") (pin "5") (pinfunction "SCL_5") (pintype "bidirectional"))
    )
    (net (code "70") (name "unconnected-(J1-SDA-Pad3)") (class "Default")
      (node (ref "J1") (pin "3") (pinfunction "SDA_3") (pintype "bidirectional"))
    )
    (net (code "71") (name "unconnected-(J2-Pad3)") (class "Default")
      (node (ref "J2") (pin "3") (pinfunction "3_3") (pintype "passive"))
    )
    (net (code "72") (name "unconnected-(J2-Pad4)") (class "Default")
      (node (ref "J2") (pin "4") (pinfunction "4_4") (pintype "passive"))
    )
    (net (code "73") (name "unconnected-(J3-Pad3)") (class "Default")
      (node (ref "J3") (pin "3") (pinfunction "3_3") (pintype "passive"))
    )
    (net (code "74") (name "unconnected-(J3-Pad4)") (class "Default")
      (node (ref "J3") (pin "4") (pinfunction "4_4") (pintype "passive"))
    )
    (net (code "75") (name "unconnected-(J4-Pad3)") (class "Default")
      (node (ref "J4") (pin "3") (pinfunction "3_3") (pintype "passive"))
    )
    (net (code "76") (name "unconnected-(J4-Pad4)") (class "Default")
      (node (ref "J4") (pin "4") (pinfunction "4_4") (pintype "passive"))
    )
    (net (code "77") (name "unconnected-(J5-Pad3)") (class "Default")
      (node (ref "J5") (pin "3") (pinfunction "3_3") (pintype "passive"))
    )
    (net (code "78") (name "unconnected-(J5-Pad4)") (class "Default")
      (node (ref "J5") (pin "4") (pinfunction "4_4") (pintype "passive"))
    )
  )
)
